# SinCos_Conditioning.net
KiCad netlist of a schematic drawn in Altium Designer
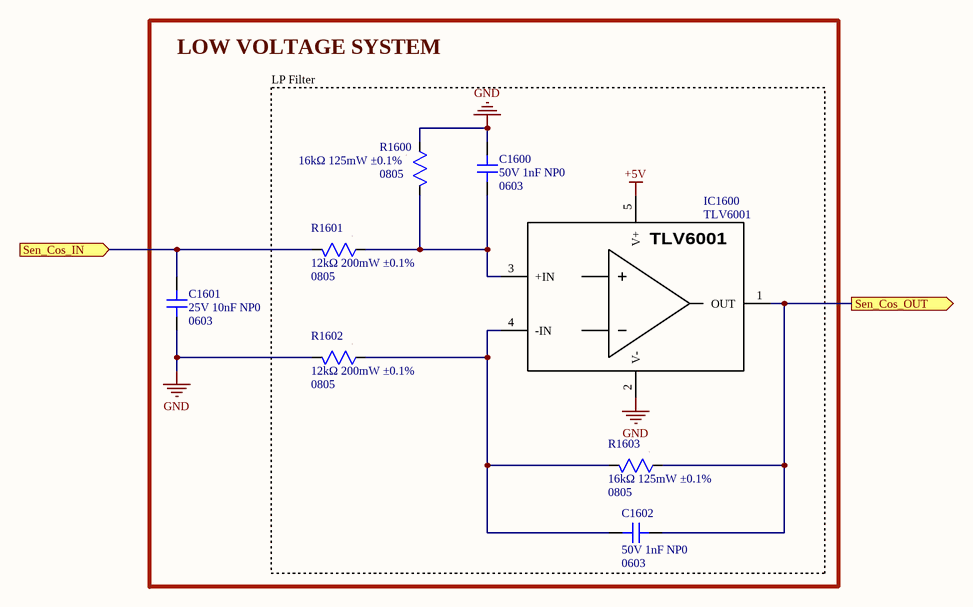
[diagram p0: SinCos_Conditioning.SchDoc]

(export (version "E")
  (design (tool "Eeschema 10.0.6"))
  (components
    (comp (ref "C1600")
      (value "50V 1nF NP0")
      (footprint "CAP SMD 0603")
      (description "Condensadores de cerámica multicapa (MLCC- SMD/SMT) WCAP-CSGP 1000pF 0603 5% 50V MLCC")
      (fields
        (field (name "PACKAGE") "0603")
        (field (name "MPN") "885012006063")
        (field (name "MANUFACTURER") "Wurth Elektronik")
      )
      (libsource (lib "eUSR_Database") (part "CAP non polarized"))
    )
    (comp (ref "C1601")
      (value "25V 10nF NP0")
      (footprint "CAP SMD 0603")
      (description "Condensadores de cerámica multicapa (MLCC- SMD/SMT) 50V 5100pF 0603 C0G 1%")
      (fields
        (field (name "PACKAGE") "0603")
        (field (name "MPN") "C0603C512F5GACTU")
        (field (name "MANUFACTURER") "KEMET")
      )
      (libsource (lib "eUSR_Database") (part "CAP non polarized"))
    )
    (comp (ref "C1602")
      (value "50V 1nF NP0")
      (footprint "CAP SMD 0603")
      (description "Condensadores de cerámica multicapa (MLCC- SMD/SMT) WCAP-CSGP 1000pF 0603 5% 50V MLCC")
      (fields
        (field (name "PACKAGE") "0603")
        (field (name "MPN") "885012006063")
        (field (name "MANUFACTURER") "Wurth Elektronik")
      )
      (libsource (lib "eUSR_Database") (part "CAP non polarized"))
    )
    (comp (ref "IC1600")
      (value "TLV6001")
      (footprint "SOT-23-5")
      (fields (field (name "MPN") "TLV6001UIDBVR") (field (name "MANUFACTURER") "Texas Instruments"))
      (libsource (lib "eUSR_Database") (part "TLV6001"))
    )
    (comp (ref "R1600")
      (value "16kΩ 125mW ±0.1%")
      (footprint "RES SMD 0805")
      (description "Resistores de película fina - SMD 0805 16Kohm 0.1% 10ppm AEC-Q200")
      (fields
        (field (name "PACKAGE") "0805")
        (field (name "MPN") "ERA-6ARB163V")
        (field (name "MANUFACTURER") "Panasonic")
      )
      (libsource (lib "eUSR_Database") (part "RES"))
    )
    (comp (ref "R1601")
      (value "12kΩ 200mW ±0.1%")
      (footprint "RES SMD 0805")
      (description "Resistores de película fina - SMD RQ 0805 12K1 0.1% 10PPM 5K RL")
      (fields
        (field (name "PACKAGE") "0805")
        (field (name "MPN") "RQ73C2A12K1BTD")
        (field (name "MANUFACTURER") "TE Connectivity / Holsworthy")
      )
      (libsource (lib "eUSR_Database") (part "RES"))
    )
    (comp (ref "R1602")
      (value "12kΩ 200mW ±0.1%")
      (footprint "RES SMD 0805")
      (description "Resistores de película fina - SMD RQ 0805 12K1 0.1% 10PPM 5K RL")
      (fields
        (field (name "PACKAGE") "0805")
        (field (name "MPN") "RQ73C2A12K1BTD")
        (field (name "MANUFACTURER") "TE Connectivity / Holsworthy")
      )
      (libsource (lib "eUSR_Database") (part "RES"))
    )
    (comp (ref "R1603")
      (value "16kΩ 125mW ±0.1%")
      (footprint "RES SMD 0805")
      (description "Resistores de película fina - SMD 0805 16Kohm 0.1% 10ppm AEC-Q200")
      (fields
        (field (name "PACKAGE") "0805")
        (field (name "MPN") "ERA-6ARB163V")
        (field (name "MANUFACTURER") "Panasonic")
      )
      (libsource (lib "eUSR_Database") (part "RES"))
    )
  )
  (nets
    (net (code "1") (name "+5V") (class "Default")
      (node (ref "IC1600") (pin "5") (pinfunction "V+_5") (pintype "passive"))
    )
    (net (code "2") (name "/Sen_Cos_IN") (class "Default")
      (node (ref "C1601") (pin "1") (pinfunction "1_1") (pintype "passive"))
      (node (ref "R1601") (pin "2") (pinfunction "2_2") (pintype "passive"))
    )
    (net (code "3") (name "/Sen_Cos_OUT") (class "Default")
      (node (ref "C1602") (pin "2") (pinfunction "2_2") (pintype "passive"))
      (node (ref "IC1600") (pin "1") (pinfunction "OUT_1") (pintype "passive"))
      (node (ref "R1603") (pin "1") (pinfunction "1_1") (pintype "passive"))
    )
    (net (code "4") (name "GND") (class "Default")
      (node (ref "C1600") (pin "2") (pinfunction "2_2") (pintype "passive"))
      (node (ref "C1601") (pin "2") (pinfunction "2_2") (pintype "passive"))
      (node (ref "IC1600") (pin "2") (pinfunction "V-_2") (pintype "passive"))
      (node (ref "R1600") (pin "1") (pinfunction "1_1") (pintype "passive"))
      (node (ref "R1602") (pin "2") (pinfunction "2_2") (pintype "passive"))
    )
    (net (code "5") (name "Net-(IC1600-+IN)") (class "Default")
      (node (ref "C1600") (pin "1") (pinfunction "1_1") (pintype "passive"))
      (node (ref "IC1600") (pin "3") (pinfunction "+IN_3") (pintype "passive"))
      (node (ref "R1600") (pin "2") (pinfunction "2_2") (pintype "passive"))
      (node (ref "R1601") (pin "1") (pinfunction "1_1") (pintype "passive"))
    )
    (net (code "6") (name "Net-(IC1600--IN)") (class "Default")
      (node (ref "C1602") (pin "1") (pinfunction "1_1") (pintype "passive"))
      (node (ref "IC1600") (pin "4") (pinfunction "-IN_4") (pintype "passive"))
      (node (ref "R1602") (pin "1") (pinfunction "1_1") (pintype "passive"))
      (node (ref "R1603") (pin "2") (pinfunction "2_2") (pintype "passive"))
    )
  )
)
